# z0-probe-v5.net
KiCad netlist of a schematic drawn in EAGLE
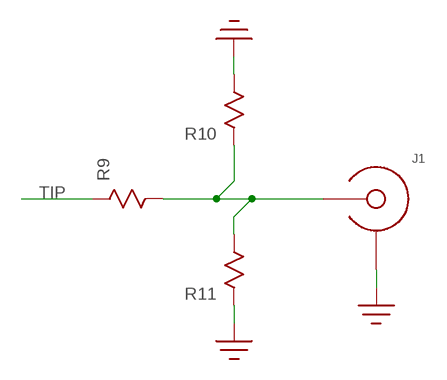
[diagram p0: schematic, sheet 1]

(export (version "E")
  (design (tool "Eeschema 10.0.6"))
  (components
    (comp (ref "J1")
      (value "SMA-EDGE-LAUNCH")
      (footprint "eagle-import:SMA_EDGE_LAUNCH_2L_4020_TAPER_FIXED")
      (libsource (lib "eagle-import") (part "SMA-EDGE-LAUNCH"))
    )
    (comp (ref "R9")
      (value "R0402-TIGHT")
      (footprint "eagle-import:0402-TIGHT")
      (libsource (lib "eagle-import") (part "R0402-TIGHT"))
    )
    (comp (ref "R10")
      (value "R0402-TIGHT")
      (footprint "eagle-import:0402-TIGHT")
      (libsource (lib "eagle-import") (part "R0402-TIGHT"))
    )
    (comp (ref "R11")
      (value "R0402-TIGHT")
      (footprint "eagle-import:0402-TIGHT")
      (libsource (lib "eagle-import") (part "R0402-TIGHT"))
    )
  )
  (nets
    (net (code "1") (name "/TIP") (class "Default")
      (node (ref "R9") (pin "P$1") (pinfunction "P$3_P$1") (pintype "bidirectional"))
    )
    (net (code "2") (name "GND") (class "Default")
      (node (ref "J1") (pin "BOTTOM_GND") (pinfunction "SHIELD_BOTTOM_GND") (pintype "bidirectional"))
      (node (ref "J1") (pin "GND@1") (pinfunction "SHIELD_GND@1") (pintype "bidirectional"))
      (node (ref "J1") (pin "GND@14") (pinfunction "SHIELD_GND@14") (pintype "bidirectional"))
      (node (ref "J1") (pin "GND@15") (pinfunction "SHIELD_GND@15") (pintype "bidirectional"))
      (node (ref "J1") (pin "GND@16") (pinfunction "SHIELD_GND@16") (pintype "bidirectional"))
      (node (ref "J1") (pin "GND@17") (pinfunction "SHIELD_GND@17") (pintype "bidirectional"))
      (node (ref "J1") (pin "GND@2") (pinfunction "SHIELD_GND@2") (pintype "bidirectional"))
      (node (ref "J1") (pin "GND@3") (pinfunction "SHIELD_GND@3") (pintype "bidirectional"))
      (node (ref "J1") (pin "GND@4") (pinfunction "SHIELD_GND@4") (pintype "bidirectional"))
      (node (ref "J1") (pin "GND@5") (pinfunction "SHIELD_GND@5") (pintype "bidirectional"))
      (node (ref "J1") (pin "GND@6") (pinfunction "SHIELD_GND@6") (pintype "bidirectional"))
      (node (ref "J1") (pin "GND@7") (pinfunction "SHIELD_GND@7") (pintype "bidirectional"))
      (node (ref "J1") (pin "GND@8") (pinfunction "SHIELD_GND@8") (pintype "bidirectional"))
      (node (ref "J1") (pin "GND_PAD1") (pinfunction "SHIELD_GND_PAD1") (pintype "bidirectional"))
      (node (ref "J1") (pin "GND_PAD2") (pinfunction "SHIELD_GND_PAD2") (pintype "bidirectional"))
      (node (ref "J1") (pin "P$1") (pinfunction "SHIELD_P$1") (pintype "bidirectional"))
      (node (ref "J1") (pin "P$2") (pinfunction "SHIELD_P$2") (pintype "bidirectional"))
      (node (ref "R10") (pin "P$2") (pinfunction "P$4_P$2") (pintype "bidirectional"))
      (node (ref "R11") (pin "P$1") (pinfunction "P$3_P$1") (pintype "bidirectional"))
    )
    (net (code "3") (name "Net-(R10-P$3)") (class "Default")
      (node (ref "J1") (pin "CENTER@1") (pinfunction "CENTER_CENTER@1") (pintype "bidirectional"))
      (node (ref "J1") (pin "P$3") (pinfunction "CENTER_P$3") (pintype "bidirectional"))
      (node (ref "R10") (pin "P$1") (pinfunction "P$3_P$1") (pintype "bidirectional"))
      (node (ref "R11") (pin "P$2") (pinfunction "P$4_P$2") (pintype "bidirectional"))
      (node (ref "R9") (pin "P$2") (pinfunction "P$4_P$2") (pintype "bidirectional"))
    )
  )
)
